# console1.net
KiCad netlist of a schematic drawn in EAGLE
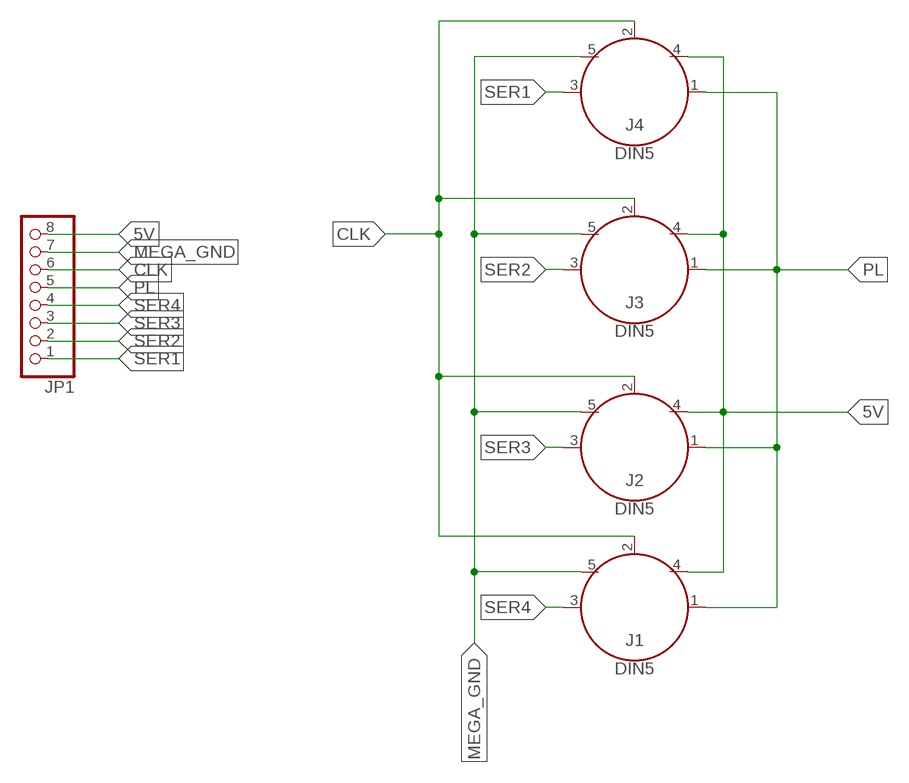
[diagram p0: schematic, sheet 1]

(export (version "E")
  (design (tool "Eeschema 10.0.6"))
  (components
    (comp (ref "J1")
      (value "DIN5")
      (footprint "eagle-import:DIN5-RA-PTH")
      (libsource (lib "eagle-import") (part "DIN5"))
    )
    (comp (ref "J2")
      (value "DIN5")
      (footprint "eagle-import:DIN5-RA-PTH")
      (libsource (lib "eagle-import") (part "DIN5"))
    )
    (comp (ref "J3")
      (value "DIN5")
      (footprint "eagle-import:DIN5-RA-PTH")
      (libsource (lib "eagle-import") (part "DIN5"))
    )
    (comp (ref "J4")
      (value "DIN5")
      (footprint "eagle-import:DIN5-RA-PTH")
      (libsource (lib "eagle-import") (part "DIN5"))
    )
    (comp (ref "JP1")
      (value "PINHD-1X8")
      (footprint "eagle-import:1X08")
      (libsource (lib "eagle-import") (part "PINHD-1X8"))
    )
  )
  (nets
    (net (code "1") (name "5V") (class "Default")
      (node (ref "J1") (pin "4") (pinfunction "4_4") (pintype "bidirectional"))
      (node (ref "J2") (pin "4") (pinfunction "4_4") (pintype "bidirectional"))
      (node (ref "J3") (pin "4") (pinfunction "4_4") (pintype "bidirectional"))
      (node (ref "J4") (pin "4") (pinfunction "4_4") (pintype "bidirectional"))
      (node (ref "JP1") (pin "8") (pinfunction "8_8") (pintype "passive"))
    )
    (net (code "2") (name "CLK") (class "Default")
      (node (ref "J1") (pin "2") (pinfunction "2_2") (pintype "bidirectional"))
      (node (ref "J2") (pin "2") (pinfunction "2_2") (pintype "bidirectional"))
      (node (ref "J3") (pin "2") (pinfunction "2_2") (pintype "bidirectional"))
      (node (ref "J4") (pin "2") (pinfunction "2_2") (pintype "bidirectional"))
      (node (ref "JP1") (pin "6") (pinfunction "6_6") (pintype "passive"))
    )
    (net (code "3") (name "MEGA_GND") (class "Default")
      (node (ref "J1") (pin "5") (pinfunction "5_5") (pintype "bidirectional"))
      (node (ref "J2") (pin "5") (pinfunction "5_5") (pintype "bidirectional"))
      (node (ref "J3") (pin "5") (pinfunction "5_5") (pintype "bidirectional"))
      (node (ref "J4") (pin "5") (pinfunction "5_5") (pintype "bidirectional"))
      (node (ref "JP1") (pin "7") (pinfunction "7_7") (pintype "passive"))
    )
    (net (code "4") (name "PL") (class "Default")
      (node (ref "J1") (pin "1") (pinfunction "1_1") (pintype "bidirectional"))
      (node (ref "J2") (pin "1") (pinfunction "1_1") (pintype "bidirectional"))
      (node (ref "J3") (pin "1") (pinfunction "1_1") (pintype "bidirectional"))
      (node (ref "J4") (pin "1") (pinfunction "1_1") (pintype "bidirectional"))
      (node (ref "JP1") (pin "5") (pinfunction "5_5") (pintype "passive"))
    )
    (net (code "5") (name "SER1") (class "Default")
      (node (ref "J4") (pin "3") (pinfunction "3_3") (pintype "bidirectional"))
      (node (ref "JP1") (pin "1") (pinfunction "1_1") (pintype "passive"))
    )
    (net (code "6") (name "SER2") (class "Default")
      (node (ref "J3") (pin "3") (pinfunction "3_3") (pintype "bidirectional"))
      (node (ref "JP1") (pin "2") (pinfunction "2_2") (pintype "passive"))
    )
    (net (code "7") (name "SER3") (class "Default")
      (node (ref "J2") (pin "3") (pinfunction "3_3") (pintype "bidirectional"))
      (node (ref "JP1") (pin "3") (pinfunction "3_3") (pintype "passive"))
    )
    (net (code "8") (name "SER4") (class "Default")
      (node (ref "J1") (pin "3") (pinfunction "3_3") (pintype "bidirectional"))
      (node (ref "JP1") (pin "4") (pinfunction "4_4") (pintype "passive"))
    )
  )
)
